# LB_BIT_o9_BARGRAPH-v02_rev1.net
KiCad netlist of a schematic drawn in EAGLE
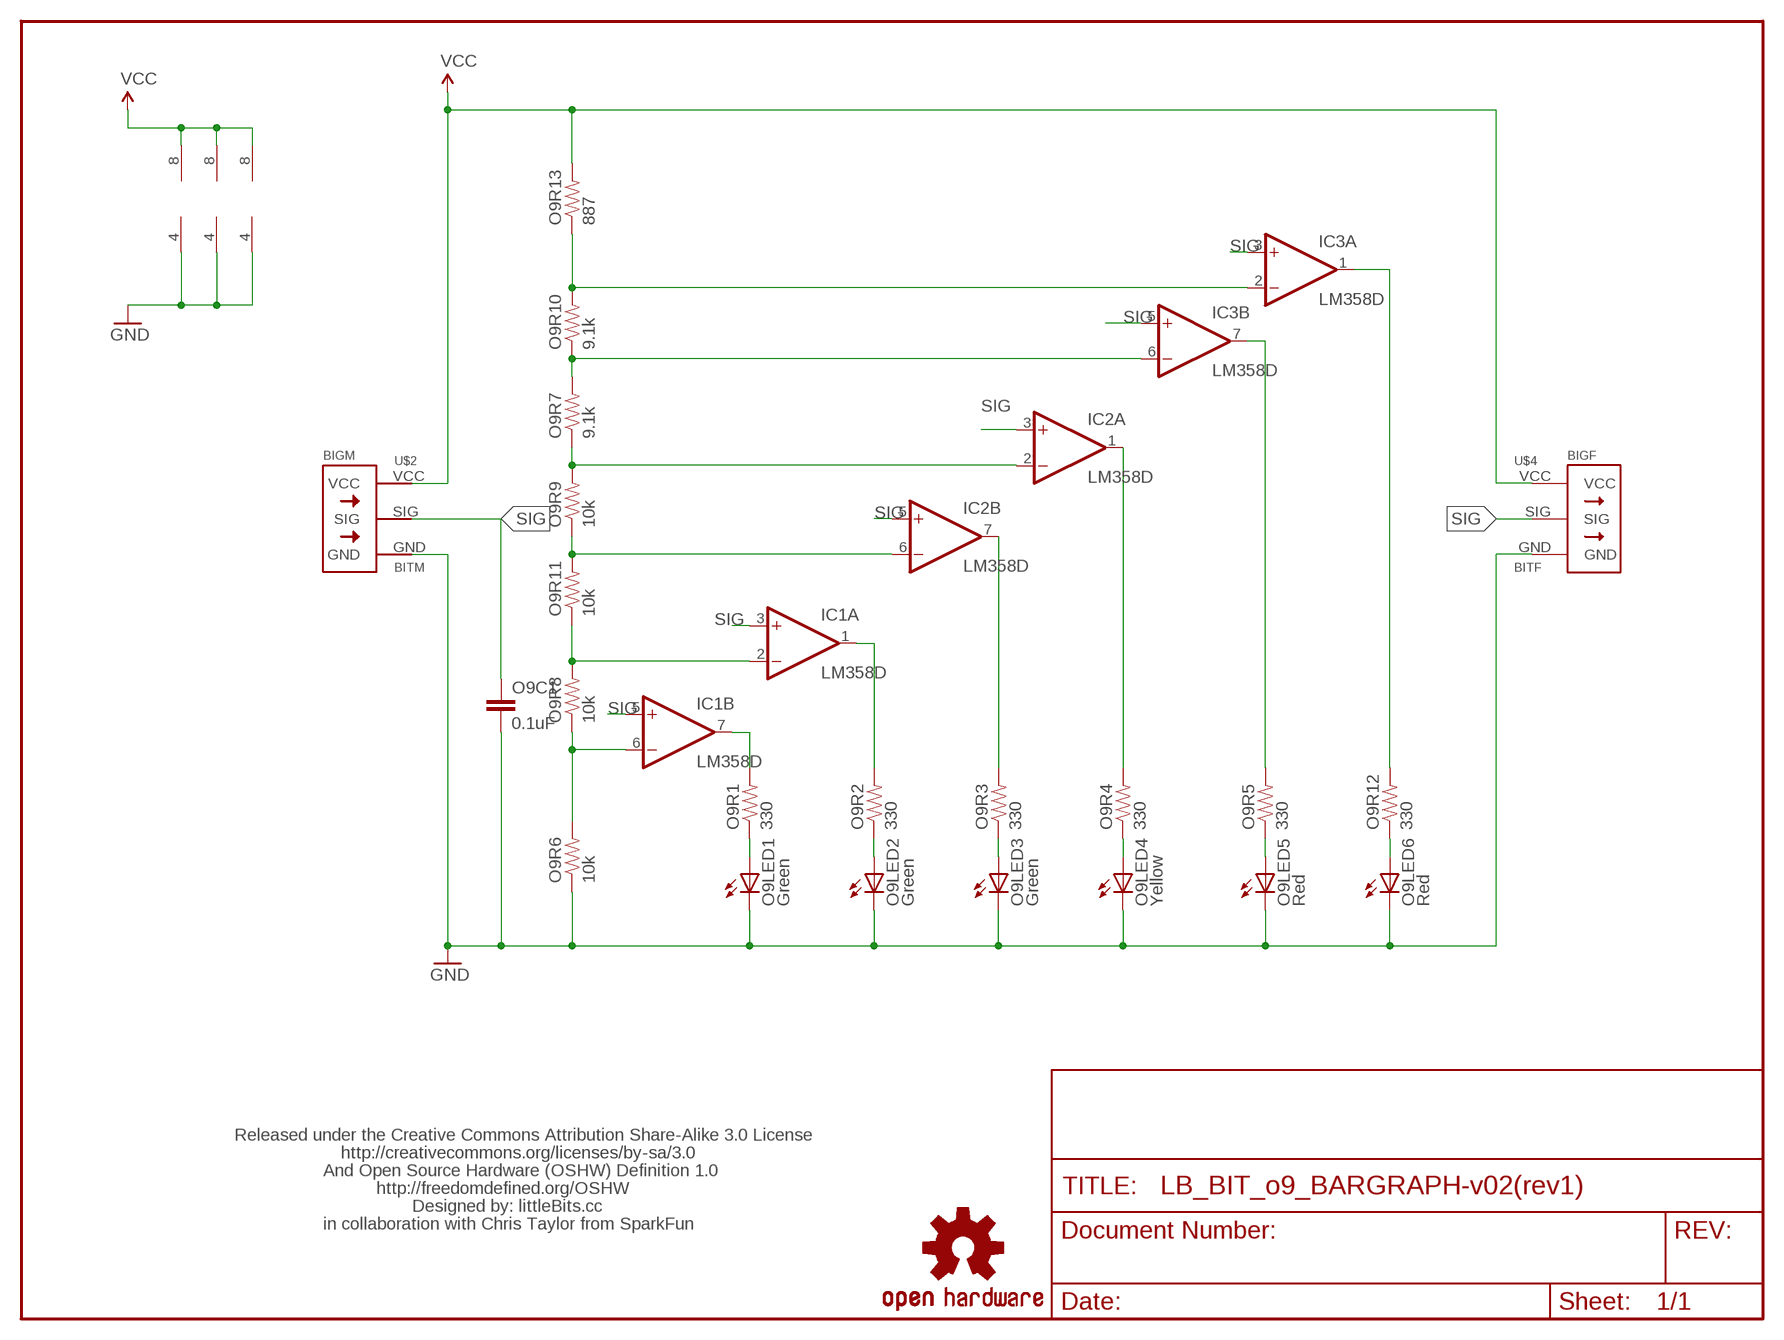
[diagram p0: schematic, sheet 1]

(export (version "E")
  (design (tool "Eeschema 10.0.6"))
  (components
    (comp (ref "IC1")
      (value "LM358D")
      (footprint "eagle-import:SO08")
      (libsource (lib "eagle-import") (part "LM358D"))
    )
    (comp (ref "IC2")
      (value "LM358D")
      (footprint "eagle-import:SO08")
      (libsource (lib "eagle-import") (part "LM358D"))
    )
    (comp (ref "IC3")
      (value "LM358D")
      (footprint "eagle-import:SO08")
      (libsource (lib "eagle-import") (part "LM358D"))
    )
    (comp (ref "O9C1")
      (value "0.1uF")
      (footprint "eagle-import:1206")
      (libsource (lib "eagle-import") (part "CAP1206"))
    )
    (comp (ref "O9LED1")
      (value "Green")
      (footprint "eagle-import:LED-1206")
      (libsource (lib "eagle-import") (part "LED1206"))
    )
    (comp (ref "O9LED2")
      (value "Green")
      (footprint "eagle-import:LED-1206")
      (libsource (lib "eagle-import") (part "LED1206"))
    )
    (comp (ref "O9LED3")
      (value "Green")
      (footprint "eagle-import:LED-1206")
      (libsource (lib "eagle-import") (part "LED1206"))
    )
    (comp (ref "O9LED4")
      (value "Yellow")
      (footprint "eagle-import:LED-1206")
      (libsource (lib "eagle-import") (part "LED1206"))
    )
    (comp (ref "O9LED5")
      (value "Red")
      (footprint "eagle-import:LED-1206")
      (libsource (lib "eagle-import") (part "LED1206"))
    )
    (comp (ref "O9LED6")
      (value "Red")
      (footprint "eagle-import:LED-1206")
      (libsource (lib "eagle-import") (part "LED1206"))
    )
    (comp (ref "O9R1")
      (value "330")
      (footprint "eagle-import:0805")
      (libsource (lib "eagle-import") (part "RESISTOR"))
    )
    (comp (ref "O9R2")
      (value "330")
      (footprint "eagle-import:0805")
      (libsource (lib "eagle-import") (part "RESISTOR"))
    )
    (comp (ref "O9R3")
      (value "330")
      (footprint "eagle-import:0805")
      (libsource (lib "eagle-import") (part "RESISTOR"))
    )
    (comp (ref "O9R4")
      (value "330")
      (footprint "eagle-import:0805")
      (libsource (lib "eagle-import") (part "RESISTOR"))
    )
    (comp (ref "O9R5")
      (value "330")
      (footprint "eagle-import:0805")
      (libsource (lib "eagle-import") (part "RESISTOR"))
    )
    (comp (ref "O9R6")
      (value "10k")
      (footprint "eagle-import:0805")
      (libsource (lib "eagle-import") (part "RESISTOR"))
    )
    (comp (ref "O9R7")
      (value "9.1k")
      (footprint "eagle-import:0805")
      (libsource (lib "eagle-import") (part "RESISTOR"))
    )
    (comp (ref "O9R8")
      (value "10k")
      (footprint "eagle-import:0805")
      (libsource (lib "eagle-import") (part "RESISTOR"))
    )
    (comp (ref "O9R9")
      (value "10k")
      (footprint "eagle-import:0805")
      (libsource (lib "eagle-import") (part "RESISTOR"))
    )
    (comp (ref "O9R10")
      (value "9.1k")
      (footprint "eagle-import:0805")
      (libsource (lib "eagle-import") (part "RESISTOR"))
    )
    (comp (ref "O9R11")
      (value "10k")
      (footprint "eagle-import:0805")
      (libsource (lib "eagle-import") (part "RESISTOR"))
    )
    (comp (ref "O9R12")
      (value "330")
      (footprint "eagle-import:0805")
      (libsource (lib "eagle-import") (part "RESISTOR"))
    )
    (comp (ref "O9R13")
      (value "887")
      (footprint "eagle-import:0805")
      (libsource (lib "eagle-import") (part "RESISTOR"))
    )
    (comp (ref "U$1")
      (value "LB_CREDITS")
      (footprint "eagle-import:OSHWCREDIT")
      (libsource (lib "eagle-import") (part "LB_CREDITS"))
    )
    (comp (ref "U$2")
      (value "BITM")
      (footprint "eagle-import:BITM")
      (libsource (lib "eagle-import") (part "BITM"))
    )
    (comp (ref "U$3")
      (value "OSHW-LOGOL")
      (footprint "eagle-import:OSHW-LOGO-L")
      (libsource (lib "eagle-import") (part "OSHW-LOGOL"))
    )
    (comp (ref "U$4")
      (value "BITF")
      (footprint "eagle-import:BITM")
      (libsource (lib "eagle-import") (part "BITF"))
    )
  )
  (nets
    (net (code "1") (name "GND") (class "Default")
      (node (ref "IC1") (pin "4") (pinfunction "V-_4") (pintype "power_in"))
      (node (ref "IC2") (pin "4") (pinfunction "V-_4") (pintype "power_in"))
      (node (ref "IC3") (pin "4") (pinfunction "V-_4") (pintype "power_in"))
      (node (ref "O9C1") (pin "2") (pinfunction "2_2") (pintype "passive"))
      (node (ref "O9LED1") (pin "C") (pinfunction "C_C") (pintype "passive"))
      (node (ref "O9LED2") (pin "C") (pinfunction "C_C") (pintype "passive"))
      (node (ref "O9LED3") (pin "C") (pinfunction "C_C") (pintype "passive"))
      (node (ref "O9LED4") (pin "C") (pinfunction "C_C") (pintype "passive"))
      (node (ref "O9LED5") (pin "C") (pinfunction "C_C") (pintype "passive"))
      (node (ref "O9LED6") (pin "C") (pinfunction "C_C") (pintype "passive"))
      (node (ref "O9R6") (pin "1") (pinfunction "1_1") (pintype "passive"))
      (node (ref "U$2") (pin "GND") (pinfunction "GND_GND") (pintype "bidirectional"))
      (node (ref "U$4") (pin "GND") (pinfunction "GND_GND") (pintype "bidirectional"))
    )
    (net (code "2") (name "Net-(IC1A--IN)") (class "Default")
      (node (ref "IC1") (pin "2") (pinfunction "-IN_2") (pintype "input"))
      (node (ref "O9R11") (pin "1") (pinfunction "1_1") (pintype "passive"))
      (node (ref "O9R8") (pin "2") (pinfunction "2_2") (pintype "passive"))
    )
    (net (code "3") (name "Net-(IC1A-OUT)") (class "Default")
      (node (ref "IC1") (pin "1") (pinfunction "OUT_1") (pintype "output"))
      (node (ref "O9R2") (pin "2") (pinfunction "2_2") (pintype "passive"))
    )
    (net (code "4") (name "Net-(IC1B--IN)") (class "Default")
      (node (ref "IC1") (pin "6") (pinfunction "-IN_6") (pintype "input"))
      (node (ref "O9R6") (pin "2") (pinfunction "2_2") (pintype "passive"))
      (node (ref "O9R8") (pin "1") (pinfunction "1_1") (pintype "passive"))
    )
    (net (code "5") (name "Net-(IC1B-OUT)") (class "Default")
      (node (ref "IC1") (pin "7") (pinfunction "OUT_7") (pintype "output"))
      (node (ref "O9R1") (pin "2") (pinfunction "2_2") (pintype "passive"))
    )
    (net (code "6") (name "Net-(IC2A--IN)") (class "Default")
      (node (ref "IC2") (pin "2") (pinfunction "-IN_2") (pintype "input"))
      (node (ref "O9R7") (pin "1") (pinfunction "1_1") (pintype "passive"))
      (node (ref "O9R9") (pin "2") (pinfunction "2_2") (pintype "passive"))
    )
    (net (code "7") (name "Net-(IC2A-OUT)") (class "Default")
      (node (ref "IC2") (pin "1") (pinfunction "OUT_1") (pintype "output"))
      (node (ref "O9R4") (pin "2") (pinfunction "2_2") (pintype "passive"))
    )
    (net (code "8") (name "Net-(IC2B--IN)") (class "Default")
      (node (ref "IC2") (pin "6") (pinfunction "-IN_6") (pintype "input"))
      (node (ref "O9R11") (pin "2") (pinfunction "2_2") (pintype "passive"))
      (node (ref "O9R9") (pin "1") (pinfunction "1_1") (pintype "passive"))
    )
    (net (code "9") (name "Net-(IC2B-OUT)") (class "Default")
      (node (ref "IC2") (pin "7") (pinfunction "OUT_7") (pintype "output"))
      (node (ref "O9R3") (pin "2") (pinfunction "2_2") (pintype "passive"))
    )
    (net (code "10") (name "Net-(IC3A--IN)") (class "Default")
      (node (ref "IC3") (pin "2") (pinfunction "-IN_2") (pintype "input"))
      (node (ref "O9R10") (pin "2") (pinfunction "2_2") (pintype "passive"))
      (node (ref "O9R13") (pin "1") (pinfunction "1_1") (pintype "passive"))
    )
    (net (code "11") (name "Net-(IC3A-OUT)") (class "Default")
      (node (ref "IC3") (pin "1") (pinfunction "OUT_1") (pintype "output"))
      (node (ref "O9R12") (pin "2") (pinfunction "2_2") (pintype "passive"))
    )
    (net (code "12") (name "Net-(IC3B--IN)") (class "Default")
      (node (ref "IC3") (pin "6") (pinfunction "-IN_6") (pintype "input"))
      (node (ref "O9R10") (pin "1") (pinfunction "1_1") (pintype "passive"))
      (node (ref "O9R7") (pin "2") (pinfunction "2_2") (pintype "passive"))
    )
    (net (code "13") (name "Net-(IC3B-OUT)") (class "Default")
      (node (ref "IC3") (pin "7") (pinfunction "OUT_7") (pintype "output"))
      (node (ref "O9R5") (pin "2") (pinfunction "2_2") (pintype "passive"))
    )
    (net (code "14") (name "Net-(O9LED1-PadA)") (class "Default")
      (node (ref "O9LED1") (pin "A") (pinfunction "A_A") (pintype "passive"))
      (node (ref "O9R1") (pin "1") (pinfunction "1_1") (pintype "passive"))
    )
    (net (code "15") (name "Net-(O9LED2-PadA)") (class "Default")
      (node (ref "O9LED2") (pin "A") (pinfunction "A_A") (pintype "passive"))
      (node (ref "O9R2") (pin "1") (pinfunction "1_1") (pintype "passive"))
    )
    (net (code "16") (name "Net-(O9LED3-PadA)") (class "Default")
      (node (ref "O9LED3") (pin "A") (pinfunction "A_A") (pintype "passive"))
      (node (ref "O9R3") (pin "1") (pinfunction "1_1") (pintype "passive"))
    )
    (net (code "17") (name "Net-(O9LED4-PadA)") (class "Default")
      (node (ref "O9LED4") (pin "A") (pinfunction "A_A") (pintype "passive"))
      (node (ref "O9R4") (pin "1") (pinfunction "1_1") (pintype "passive"))
    )
    (net (code "18") (name "Net-(O9LED5-PadA)") (class "Default")
      (node (ref "O9LED5") (pin "A") (pinfunction "A_A") (pintype "passive"))
      (node (ref "O9R5") (pin "1") (pinfunction "1_1") (pintype "passive"))
    )
    (net (code "19") (name "Net-(O9LED6-PadA)") (class "Default")
      (node (ref "O9LED6") (pin "A") (pinfunction "A_A") (pintype "passive"))
      (node (ref "O9R12") (pin "1") (pinfunction "1_1") (pintype "passive"))
    )
    (net (code "20") (name "SIG") (class "Default")
      (node (ref "IC1") (pin "3") (pinfunction "+IN_3") (pintype "input"))
      (node (ref "IC1") (pin "5") (pinfunction "+IN_5") (pintype "input"))
      (node (ref "IC2") (pin "3") (pinfunction "+IN_3") (pintype "input"))
      (node (ref "IC2") (pin "5") (pinfunction "+IN_5") (pintype "input"))
      (node (ref "IC3") (pin "3") (pinfunction "+IN_3") (pintype "input"))
      (node (ref "IC3") (pin "5") (pinfunction "+IN_5") (pintype "input"))
      (node (ref "O9C1") (pin "1") (pinfunction "1_1") (pintype "passive"))
      (node (ref "U$2") (pin "SIG") (pinfunction "SIG_SIG") (pintype "bidirectional"))
      (node (ref "U$4") (pin "SIG") (pinfunction "SIG_SIG") (pintype "bidirectional"))
    )
    (net (code "21") (name "VCC") (class "Default")
      (node (ref "IC1") (pin "8") (pinfunction "V+_8") (pintype "power_in"))
      (node (ref "IC2") (pin "8") (pinfunction "V+_8") (pintype "power_in"))
      (node (ref "IC3") (pin "8") (pinfunction "V+_8") (pintype "power_in"))
      (node (ref "O9R13") (pin "2") (pinfunction "2_2") (pintype "passive"))
      (node (ref "U$2") (pin "VCC") (pinfunction "VCC_VCC") (pintype "bidirectional"))
      (node (ref "U$4") (pin "VCC") (pinfunction "VCC_VCC") (pintype "bidirectional"))
    )
  )
)
